# LPC_Rep.net
KiCad netlist of a schematic drawn in Altium Designer
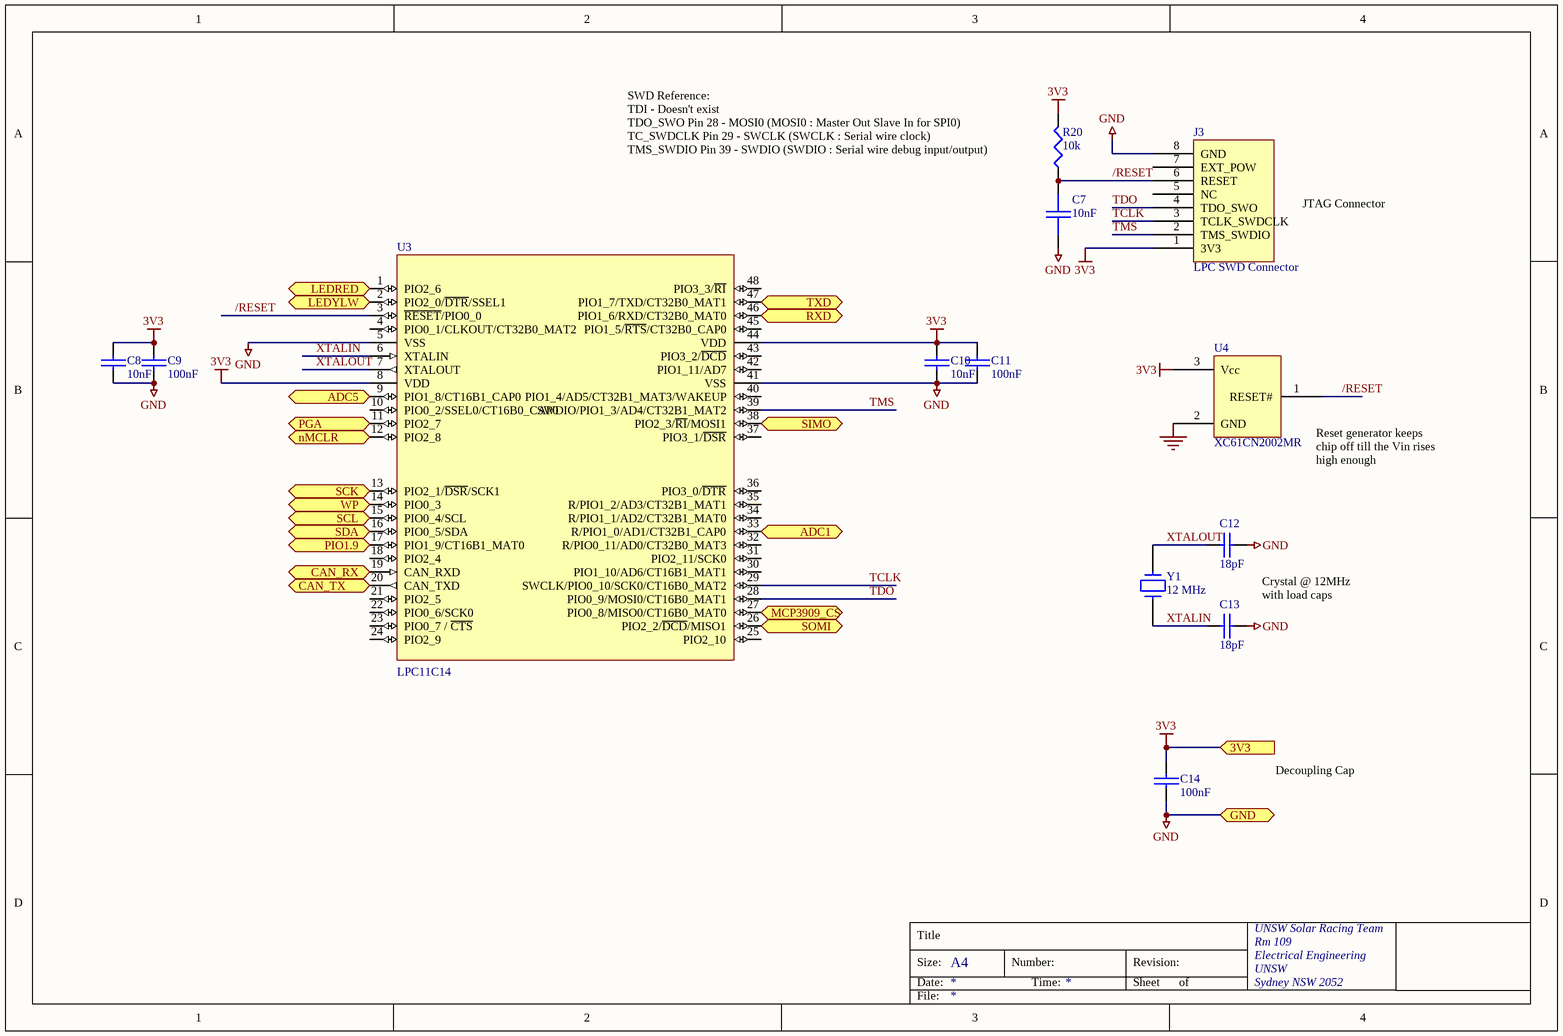
[diagram p0: LPC_Rep.SchDoc]

(export (version "E")
  (design (tool "Eeschema 10.0.6"))
  (components
    (comp (ref "C7")
      (value "10nF")
      (footprint "0603")
      (description "Capacitor")
      (libsource (lib "SunswiftLib20030312RR") (part "CAP"))
    )
    (comp (ref "C8")
      (value "10nF")
      (footprint "0603")
      (description "Capacitor")
      (libsource (lib "*") (part "CAP"))
    )
    (comp (ref "C9")
      (value "100nF")
      (footprint "0603")
      (description "Capacitor")
      (libsource (lib "*") (part "CAP"))
    )
    (comp (ref "C10")
      (value "10nF")
      (footprint "0603")
      (description "Capacitor")
      (libsource (lib "*") (part "CAP"))
    )
    (comp (ref "C11")
      (value "100nF")
      (footprint "0603")
      (description "Capacitor")
      (libsource (lib "*") (part "CAP"))
    )
    (comp (ref "C12")
      (value "18pF")
      (footprint "0603")
      (description "Capacitor")
      (libsource (lib "*") (part "CAP"))
    )
    (comp (ref "C13")
      (value "18pF")
      (footprint "0603")
      (description "Capacitor")
      (libsource (lib "*") (part "CAP"))
    )
    (comp (ref "C14")
      (value "100nF")
      (footprint "0603")
      (description "Capacitor")
      (libsource (lib "*") (part "CAP"))
    )
    (comp (ref "J3")
      (value "LPC SWD Connector")
      (footprint "IDC8")
      (libsource (lib "2009_BatteryMaster") (part "LPCLink_Connector"))
    )
    (comp (ref "R20")
      (value "10k")
      (footprint "0603")
      (description "Resistor")
      (libsource (lib "SunswiftLib20030312RR") (part "RES1"))
    )
    (comp (ref "U3")
      (value "LPC11C14")
      (footprint "Quad48-LPC11c14")
      (libsource (lib "LPC") (part "LPC11C14_Full"))
    )
    (comp (ref "U4")
      (value "XC61CN2002MR")
      (footprint "SOT23-3")
      (description "SOT23 reset generator")
      (libsource (lib "*") (part "XC61F"))
    )
    (comp (ref "Y1")
      (value "12 MHz")
      (footprint "HC49/4H")
      (description "Crystal")
      (libsource (lib "*") (part "CRYSTAL"))
    )
  )
  (nets
    (net (code "1") (name "/ADC1") (class "Default")
      (node (ref "U3") (pin "33") (pinfunction "R/PIO1_0/AD1/CT32B1_CAP0_33") (pintype "bidirectional"))
    )
    (net (code "2") (name "/ADC5") (class "Default")
      (node (ref "U3") (pin "9") (pinfunction "PIO1_8/CT16B1_CAP0_9") (pintype "bidirectional"))
    )
    (net (code "3") (name "/CAN_RX") (class "Default")
      (node (ref "U3") (pin "19") (pinfunction "CAN_RXD_19") (pintype "input"))
    )
    (net (code "4") (name "/CAN_TX") (class "Default")
      (node (ref "U3") (pin "20") (pinfunction "CAN_TXD_20") (pintype "output"))
    )
    (net (code "5") (name "/LEDRED") (class "Default")
      (node (ref "U3") (pin "1") (pinfunction "PIO2_6_1") (pintype "bidirectional"))
    )
    (net (code "6") (name "/LEDYLW") (class "Default")
      (node (ref "U3") (pin "2") (pinfunction "PIO2_0/~{DTR}/SSEL1_2") (pintype "bidirectional"))
    )
    (net (code "7") (name "/MCP3909_CS") (class "Default")
      (node (ref "U3") (pin "27") (pinfunction "PIO0_8/MISO0/CT16B0_MAT0_27") (pintype "bidirectional"))
    )
    (net (code "8") (name "/PGA") (class "Default")
      (node (ref "U3") (pin "11") (pinfunction "PIO2_7_11") (pintype "bidirectional"))
    )
    (net (code "9") (name "/PIO1.9") (class "Default")
      (node (ref "U3") (pin "17") (pinfunction "PIO1_9/CT16B1_MAT0_17") (pintype "bidirectional"))
    )
    (net (code "10") (name "/RXD") (class "Default")
      (node (ref "U3") (pin "46") (pinfunction "PIO1_6/RXD/CT32B0_MAT0_46") (pintype "bidirectional"))
    )
    (net (code "11") (name "/SCK") (class "Default")
      (node (ref "U3") (pin "13") (pinfunction "PIO2_1/~{DSR}/SCK1_13") (pintype "bidirectional"))
    )
    (net (code "12") (name "/SCL") (class "Default")
      (node (ref "U3") (pin "15") (pinfunction "PIO0_4/SCL_15") (pintype "bidirectional"))
    )
    (net (code "13") (name "/SDA") (class "Default")
      (node (ref "U3") (pin "16") (pinfunction "PIO0_5/SDA_16") (pintype "bidirectional"))
    )
    (net (code "14") (name "/SIMO") (class "Default")
      (node (ref "U3") (pin "38") (pinfunction "PIO2_3/~{RI}/MOSI1_38") (pintype "bidirectional"))
    )
    (net (code "15") (name "/SOMI") (class "Default")
      (node (ref "U3") (pin "26") (pinfunction "PIO2_2/~{DCD}/MISO1_26") (pintype "bidirectional"))
    )
    (net (code "16") (name "/TCLK") (class "Default")
      (node (ref "J3") (pin "3") (pinfunction "TCLK_SWDCLK_3") (pintype "passive"))
      (node (ref "U3") (pin "29") (pinfunction "SWCLK/PIO0_10/SCK0/CT16B0_MAT2_29") (pintype "bidirectional"))
    )
    (net (code "17") (name "/TDO") (class "Default")
      (node (ref "J3") (pin "4") (pinfunction "TDO_SWO_4") (pintype "passive"))
      (node (ref "U3") (pin "28") (pinfunction "PIO0_9/MOSI0/CT16B0_MAT1_28") (pintype "bidirectional"))
    )
    (net (code "18") (name "/TMS") (class "Default")
      (node (ref "J3") (pin "2") (pinfunction "TMS_SWDIO_2") (pintype "passive"))
      (node (ref "U3") (pin "39") (pinfunction "SWDIO/PIO1_3/AD4/CT32B1_MAT2_39") (pintype "bidirectional"))
    )
    (net (code "19") (name "/TXD") (class "Default")
      (node (ref "U3") (pin "47") (pinfunction "PIO1_7/TXD/CT32B0_MAT1_47") (pintype "bidirectional"))
    )
    (net (code "20") (name "/WP") (class "Default")
      (node (ref "U3") (pin "14") (pinfunction "PIO0_3_14") (pintype "bidirectional"))
    )
    (net (code "21") (name "/XTALIN") (class "Default")
      (node (ref "C13") (pin "1") (pinfunction "1_1") (pintype "passive"))
      (node (ref "U3") (pin "6") (pinfunction "XTALIN_6") (pintype "input"))
      (node (ref "Y1") (pin "1") (pinfunction "1_1") (pintype "passive"))
    )
    (net (code "22") (name "/XTALOUT") (class "Default")
      (node (ref "C12") (pin "1") (pinfunction "1_1") (pintype "passive"))
      (node (ref "U3") (pin "7") (pinfunction "XTALOUT_7") (pintype "output"))
      (node (ref "Y1") (pin "2") (pinfunction "2_2") (pintype "passive"))
    )
    (net (code "23") (name "/nMCLR") (class "Default")
      (node (ref "U3") (pin "12") (pinfunction "PIO2_8_12") (pintype "bidirectional"))
    )
    (net (code "24") (name "/{slash}RESET") (class "Default")
      (node (ref "C7") (pin "1") (pinfunction "1_1") (pintype "passive"))
      (node (ref "J3") (pin "6") (pinfunction "RESET_6") (pintype "passive"))
      (node (ref "R20") (pin "1") (pinfunction "1_1") (pintype "passive"))
      (node (ref "U3") (pin "3") (pinfunction "~{RESET}/PIO0_0_3") (pintype "bidirectional"))
      (node (ref "U4") (pin "1") (pinfunction "RESET#_1") (pintype "passive"))
    )
    (net (code "25") (name "3V3") (class "Default")
      (node (ref "C10") (pin "2") (pinfunction "2_2") (pintype "passive"))
      (node (ref "C11") (pin "2") (pinfunction "2_2") (pintype "passive"))
      (node (ref "C14") (pin "1") (pinfunction "1_1") (pintype "passive"))
      (node (ref "C8") (pin "2") (pinfunction "2_2") (pintype "passive"))
      (node (ref "C9") (pin "2") (pinfunction "2_2") (pintype "passive"))
      (node (ref "J3") (pin "1") (pinfunction "3V3_1") (pintype "passive"))
      (node (ref "R20") (pin "2") (pinfunction "2_2") (pintype "passive"))
      (node (ref "U3") (pin "44") (pinfunction "VDD_44") (pintype "power_in"))
      (node (ref "U3") (pin "8") (pinfunction "VDD_8") (pintype "power_in"))
      (node (ref "U4") (pin "3") (pinfunction "Vcc_3") (pintype "passive"))
    )
    (net (code "26") (name "GND") (class "Default")
      (node (ref "C10") (pin "1") (pinfunction "1_1") (pintype "passive"))
      (node (ref "C11") (pin "1") (pinfunction "1_1") (pintype "passive"))
      (node (ref "C12") (pin "2") (pinfunction "2_2") (pintype "passive"))
      (node (ref "C13") (pin "2") (pinfunction "2_2") (pintype "passive"))
      (node (ref "C14") (pin "2") (pinfunction "2_2") (pintype "passive"))
      (node (ref "C7") (pin "2") (pinfunction "2_2") (pintype "passive"))
      (node (ref "C8") (pin "1") (pinfunction "1_1") (pintype "passive"))
      (node (ref "C9") (pin "1") (pinfunction "1_1") (pintype "passive"))
      (node (ref "J3") (pin "8") (pinfunction "GND_8") (pintype "passive"))
      (node (ref "U3") (pin "41") (pinfunction "VSS_41") (pintype "power_in"))
      (node (ref "U3") (pin "5") (pinfunction "VSS_5") (pintype "power_in"))
      (node (ref "U4") (pin "2") (pinfunction "GND_2") (pintype "passive"))
    )
    (net (code "27") (name "unconnected-(J3-EXT_POW-Pad7)") (class "Default")
      (node (ref "J3") (pin "7") (pinfunction "EXT_POW_7") (pintype "passive"))
    )
    (net (code "28") (name "unconnected-(J3-NC-Pad5)") (class "Default")
      (node (ref "J3") (pin "5") (pinfunction "NC_5") (pintype "passive"))
    )
    (net (code "29") (name "unconnected-(U3-PIO0_1{slash}CLKOUT{slash}CT32B0_MAT2-Pad4)") (class "Default")
      (node (ref "U3") (pin "4") (pinfunction "PIO0_1/CLKOUT/CT32B0_MAT2_4") (pintype "bidirectional"))
    )
    (net (code "30") (name "unconnected-(U3-PIO0_2{slash}SSEL0{slash}CT16B0_CAP0-Pad10)") (class "Default")
      (node (ref "U3") (pin "10") (pinfunction "PIO0_2/SSEL0/CT16B0_CAP0_10") (pintype "bidirectional"))
    )
    (net (code "31") (name "unconnected-(U3-PIO0_6{slash}SCK0-Pad22)") (class "Default")
      (node (ref "U3") (pin "22") (pinfunction "PIO0_6/SCK0_22") (pintype "bidirectional"))
    )
    (net (code "32") (name "unconnected-(U3-PIO0_7_{slash}_~{CTS}-Pad23)") (class "Default")
      (node (ref "U3") (pin "23") (pinfunction "PIO0_7_/_~{CTS}_23") (pintype "bidirectional"))
    )
    (net (code "33") (name "unconnected-(U3-PIO1_4{slash}AD5{slash}CT32B1_MAT3{slash}WAKEUP-Pad40)") (class "Default")
      (node (ref "U3") (pin "40") (pinfunction "PIO1_4/AD5/CT32B1_MAT3/WAKEUP_40") (pintype "bidirectional"))
    )
    (net (code "34") (name "unconnected-(U3-PIO1_5{slash}~{RTS}{slash}CT32B0_CAP0-Pad45)") (class "Default")
      (node (ref "U3") (pin "45") (pinfunction "PIO1_5/~{RTS}/CT32B0_CAP0_45") (pintype "bidirectional"))
    )
    (net (code "35") (name "unconnected-(U3-PIO1_10{slash}AD6{slash}CT16B1_MAT1-Pad30)") (class "Default")
      (node (ref "U3") (pin "30") (pinfunction "PIO1_10/AD6/CT16B1_MAT1_30") (pintype "bidirectional"))
    )
    (net (code "36") (name "unconnected-(U3-PIO1_11{slash}AD7-Pad42)") (class "Default")
      (node (ref "U3") (pin "42") (pinfunction "PIO1_11/AD7_42") (pintype "bidirectional"))
    )
    (net (code "37") (name "unconnected-(U3-PIO2_4-Pad18)") (class "Default")
      (node (ref "U3") (pin "18") (pinfunction "PIO2_4_18") (pintype "bidirectional"))
    )
    (net (code "38") (name "unconnected-(U3-PIO2_5-Pad21)") (class "Default")
      (node (ref "U3") (pin "21") (pinfunction "PIO2_5_21") (pintype "bidirectional"))
    )
    (net (code "39") (name "unconnected-(U3-PIO2_9-Pad24)") (class "Default")
      (node (ref "U3") (pin "24") (pinfunction "PIO2_9_24") (pintype "bidirectional"))
    )
    (net (code "40") (name "unconnected-(U3-PIO2_10-Pad25)") (class "Default")
      (node (ref "U3") (pin "25") (pinfunction "PIO2_10_25") (pintype "bidirectional"))
    )
    (net (code "41") (name "unconnected-(U3-PIO2_11{slash}SCK0-Pad31)") (class "Default")
      (node (ref "U3") (pin "31") (pinfunction "PIO2_11/SCK0_31") (pintype "bidirectional"))
    )
    (net (code "42") (name "unconnected-(U3-PIO3_0{slash}~{DTR}-Pad36)") (class "Default")
      (node (ref "U3") (pin "36") (pinfunction "PIO3_0/~{DTR}_36") (pintype "bidirectional"))
    )
    (net (code "43") (name "unconnected-(U3-PIO3_1{slash}~{DSR}-Pad37)") (class "Default")
      (node (ref "U3") (pin "37") (pinfunction "PIO3_1/~{DSR}_37") (pintype "bidirectional"))
    )
    (net (code "44") (name "unconnected-(U3-PIO3_2{slash}~{DCD}-Pad43)") (class "Default")
      (node (ref "U3") (pin "43") (pinfunction "PIO3_2/~{DCD}_43") (pintype "bidirectional"))
    )
    (net (code "45") (name "unconnected-(U3-PIO3_3{slash}~{RI}-Pad48)") (class "Default")
      (node (ref "U3") (pin "48") (pinfunction "PIO3_3/~{RI}_48") (pintype "bidirectional"))
    )
    (net (code "46") (name "unconnected-(U3-R{slash}PIO0_11{slash}AD0{slash}CT32B0_MAT3-Pad32)") (class "Default")
      (node (ref "U3") (pin "32") (pinfunction "R/PIO0_11/AD0/CT32B0_MAT3_32") (pintype "bidirectional"))
    )
    (net (code "47") (name "unconnected-(U3-R{slash}PIO1_1{slash}AD2{slash}CT32B1_MAT0-Pad34)") (class "Default")
      (node (ref "U3") (pin "34") (pinfunction "R/PIO1_1/AD2/CT32B1_MAT0_34") (pintype "bidirectional"))
    )
    (net (code "48") (name "unconnected-(U3-R{slash}PIO1_2{slash}AD3{slash}CT32B1_MAT1-Pad35)") (class "Default")
      (node (ref "U3") (pin "35") (pinfunction "R/PIO1_2/AD3/CT32B1_MAT1_35") (pintype "bidirectional"))
    )
  )
)
